# power_section.net
KiCad netlist of a schematic drawn in Altium Designer
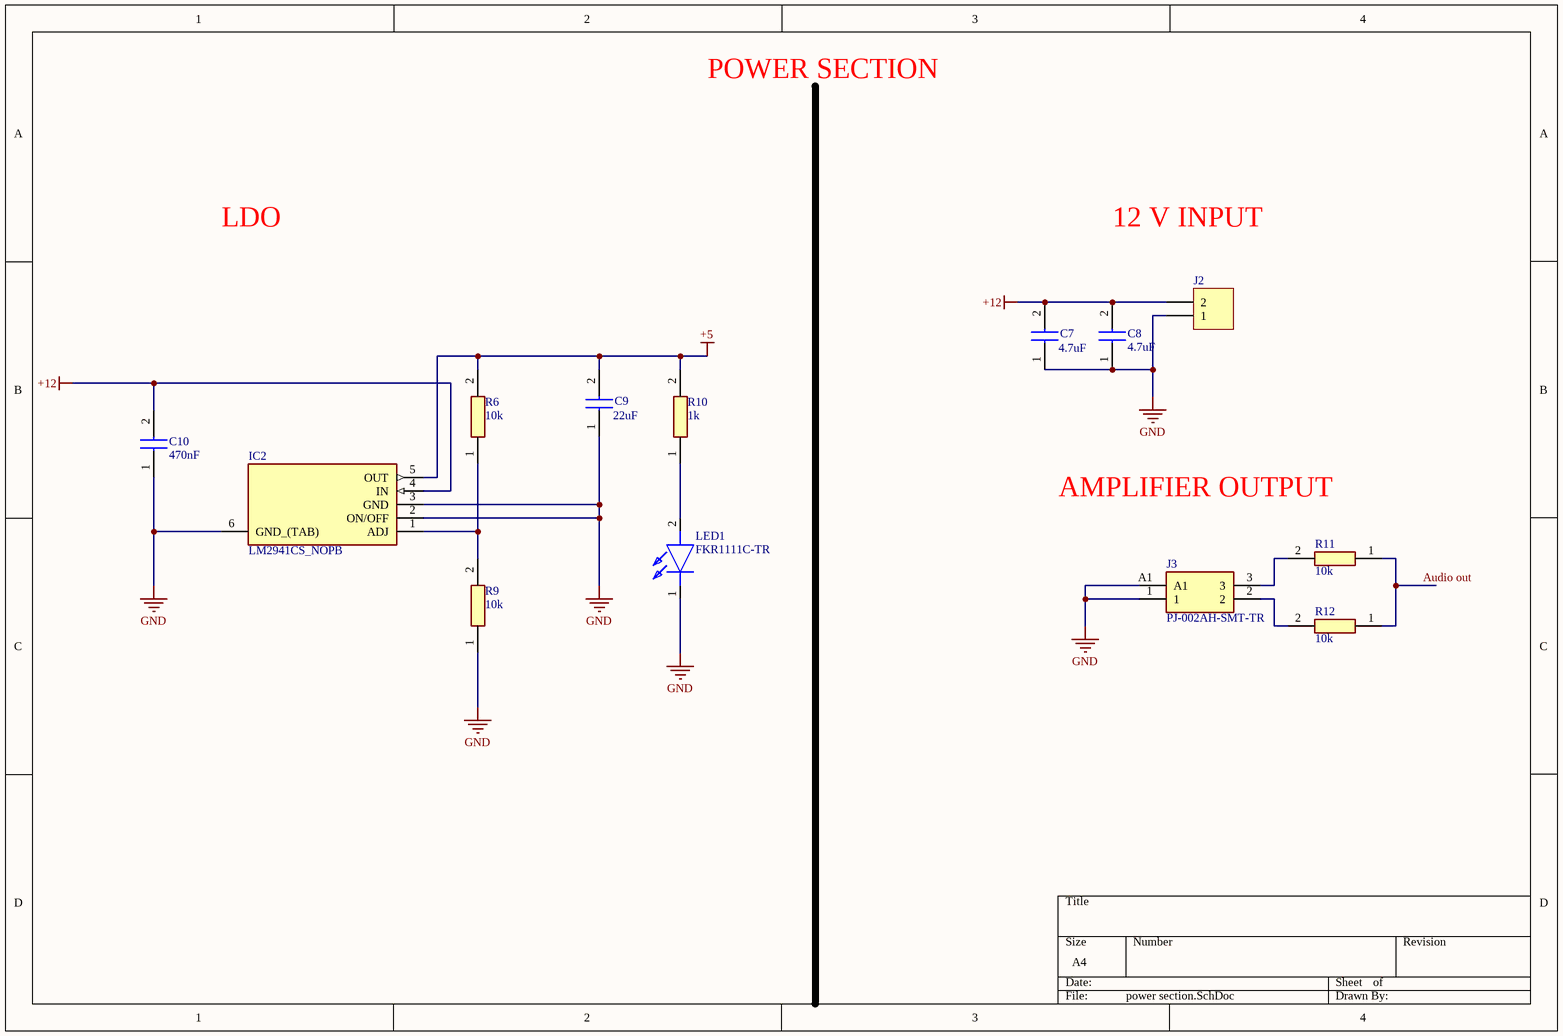
[diagram p0: power section.SchDoc]

(export (version "E")
  (design (tool "Eeschema 10.0.6"))
  (components
    (comp (ref "C7")
      (value "4.7uF")
      (footprint "SamacSys:CAPC1608X90N")
      (description "Capacitor")
      (fields
        (field (name "MANUFACTURER_PART_NUMBER") "GRM188R71C104MA01D")
        (field (name "MOUSER PART NUMBER") "81-GRM18R71C104MA01D")
      )
      (libsource (lib "SamacSys") (part "GRM188R71C104MA01D"))
    )
    (comp (ref "C8")
      (value "4.7uF")
      (footprint "SamacSys:CAPC1608X90N")
      (description "Capacitor")
      (fields
        (field (name "MANUFACTURER_PART_NUMBER") "GRM188R71C104MA01D")
        (field (name "MOUSER PART NUMBER") "81-GRM18R71C104MA01D")
      )
      (libsource (lib "SamacSys") (part "GRM188R71C104MA01D"))
    )
    (comp (ref "C9")
      (value "22uF")
      (footprint "SamacSys:CAPC1608X90N")
      (description "Capacitor")
      (fields
        (field (name "MANUFACTURER_PART_NUMBER") "GRM188R71C104MA01D")
        (field (name "MOUSER PART NUMBER") "81-GRM18R71C104MA01D")
      )
      (libsource (lib "SamacSys") (part "GRM188R71C104MA01D"))
    )
    (comp (ref "C10")
      (value "470nF")
      (footprint "SamacSys:CAPC1608X90N")
      (description "Capacitor")
      (fields
        (field (name "MANUFACTURER_PART_NUMBER") "GRM188R71C104MA01D")
        (field (name "MOUSER PART NUMBER") "81-GRM18R71C104MA01D")
      )
      (libsource (lib "SamacSys") (part "GRM188R71C104MA01D"))
    )
    (comp (ref "IC2")
      (value "LM2941CS_NOPB")
      (footprint "SamacSys:TO170P1435X465-6N")
      (description "Integrated Circuit")
      (fields
        (field (name "MANUFACTURER_PART_NUMBER") "LM2941CS/NOPB")
        (field (name "MOUSER PART NUMBER") "926-LM2941CS/NOPB")
      )
      (libsource (lib "*") (part "LM2941CS_NOPB"))
    )
    (comp (ref "J2")
      (value "~")
      (footprint "CON2_P196_1729128_TH_ST")
      (description "2 Pins, 1 Row 5mm Pitch, straight Connector, male")
      (fields
        (field (name "MANUFACTURER") "Phoenix Contact")
        (field (name "MANUFACTURER PART NUMBER") "MKDSN1,5/2")
      )
      (libsource (lib "CONTROLYTICS") (part "CON-TB_2X1-196-ST-TH"))
    )
    (comp (ref "J3")
      (value "PJ-002AH-SMT-TR")
      (footprint "SamacSys:PJ002AHSMTTR")
      (description "Connector")
      (fields (field (name "MOUSER PART NUMBER") "490-PJ-002AH-SMT-TR"))
      (libsource (lib "SamacSys") (part "PJ-002AH-SMT-TR"))
    )
    (comp (ref "LED1")
      (value "FKR1111C-TR")
      (footprint "SamacSys:LEDC1608X80N")
      (description "LED")
      (fields (field (name "MOUSER PART NUMBER") "327-FKR1111CTR"))
      (libsource (lib "SamacSys") (part "FKR1111C-TR"))
    )
    (comp (ref "R6")
      (value "10k")
      (footprint "SamacSys:ERA3AEB101V")
      (description "Resistor")
      (fields
        (field (name "MANUFACTURER_PART_NUMBER") "ERA-3AED102V")
        (field (name "MOUSER PART NUMBER") "667-ERA-3AED102V")
      )
      (libsource (lib "SamacSys") (part "ERA-3AED102V"))
    )
    (comp (ref "R9")
      (value "10k")
      (footprint "SamacSys:ERA3AEB101V")
      (description "Resistor")
      (fields
        (field (name "MANUFACTURER_PART_NUMBER") "ERA-3AED102V")
        (field (name "MOUSER PART NUMBER") "667-ERA-3AED102V")
      )
      (libsource (lib "SamacSys") (part "ERA-3AED102V"))
    )
    (comp (ref "R10")
      (value "1k")
      (footprint "SamacSys:ERA3AEB101V")
      (description "Resistor")
      (fields
        (field (name "MANUFACTURER_PART_NUMBER") "ERA-3AED102V")
        (field (name "MOUSER PART NUMBER") "667-ERA-3AED102V")
      )
      (libsource (lib "SamacSys") (part "ERA-3AED102V"))
    )
    (comp (ref "R11")
      (value "10k")
      (footprint "SamacSys:ERA3AEB101V")
      (description "Resistor")
      (fields
        (field (name "MANUFACTURER_PART_NUMBER") "ERA-3AED102V")
        (field (name "MOUSER PART NUMBER") "667-ERA-3AED102V")
      )
      (libsource (lib "") (part "ERA-3AED102V_1"))
    )
    (comp (ref "R12")
      (value "10k")
      (footprint "SamacSys:ERA3AEB101V")
      (description "Resistor")
      (fields
        (field (name "MANUFACTURER_PART_NUMBER") "ERA-3AED102V")
        (field (name "MOUSER PART NUMBER") "667-ERA-3AED102V")
      )
      (libsource (lib "") (part "ERA-3AED102V_1"))
    )
  )
  (nets
    (net (code "1") (name "+5") (class "Default")
      (node (ref "C9") (pin "2") (pinfunction "2_2") (pintype "passive"))
      (node (ref "IC2") (pin "5") (pinfunction "OUT_5") (pintype "output"))
      (node (ref "R10") (pin "2") (pinfunction "2_2") (pintype "passive"))
      (node (ref "R6") (pin "2") (pinfunction "2_2") (pintype "passive"))
    )
    (net (code "2") (name "+12") (class "Default")
      (node (ref "C10") (pin "2") (pinfunction "2_2") (pintype "passive"))
      (node (ref "C7") (pin "2") (pinfunction "2_2") (pintype "passive"))
      (node (ref "C8") (pin "2") (pinfunction "2_2") (pintype "passive"))
      (node (ref "IC2") (pin "4") (pinfunction "IN_4") (pintype "input"))
      (node (ref "J2") (pin "2") (pinfunction "2_2") (pintype "passive"))
    )
    (net (code "3") (name "/Audio out") (class "Default")
      (node (ref "R11") (pin "1") (pinfunction "1_1") (pintype "passive"))
      (node (ref "R12") (pin "1") (pinfunction "1_1") (pintype "passive"))
    )
    (net (code "4") (name "GND") (class "Default")
      (node (ref "C10") (pin "1") (pinfunction "1_1") (pintype "passive"))
      (node (ref "C7") (pin "1") (pinfunction "1_1") (pintype "passive"))
      (node (ref "C8") (pin "1") (pinfunction "1_1") (pintype "passive"))
      (node (ref "C9") (pin "1") (pinfunction "1_1") (pintype "passive"))
      (node (ref "IC2") (pin "2") (pinfunction "ON/OFF_2") (pintype "passive"))
      (node (ref "IC2") (pin "3") (pinfunction "GND_3") (pintype "power_in"))
      (node (ref "IC2") (pin "6") (pinfunction "GND_(TAB)_6") (pintype "power_in"))
      (node (ref "J2") (pin "1") (pinfunction "1_1") (pintype "passive"))
      (node (ref "J3") (pin "1") (pinfunction "1_1") (pintype "passive"))
      (node (ref "J3") (pin "A1") (pinfunction "A1_A1") (pintype "passive"))
      (node (ref "LED1") (pin "1") (pinfunction "K_1") (pintype "passive"))
      (node (ref "R9") (pin "1") (pinfunction "1_1") (pintype "passive"))
    )
    (net (code "5") (name "Net-(IC2-ADJ)") (class "Default")
      (node (ref "IC2") (pin "1") (pinfunction "ADJ_1") (pintype "passive"))
      (node (ref "R6") (pin "1") (pinfunction "1_1") (pintype "passive"))
      (node (ref "R9") (pin "2") (pinfunction "2_2") (pintype "passive"))
    )
    (net (code "6") (name "Net-(J3-Pad2)") (class "Default")
      (node (ref "J3") (pin "2") (pinfunction "2_2") (pintype "passive"))
      (node (ref "R12") (pin "2") (pinfunction "2_2") (pintype "passive"))
    )
    (net (code "7") (name "Net-(J3-Pad3)") (class "Default")
      (node (ref "J3") (pin "3") (pinfunction "3_3") (pintype "passive"))
      (node (ref "R11") (pin "2") (pinfunction "2_2") (pintype "passive"))
    )
    (net (code "8") (name "Net-(LED1-A)") (class "Default")
      (node (ref "LED1") (pin "2") (pinfunction "A_2") (pintype "passive"))
      (node (ref "R10") (pin "1") (pinfunction "1_1") (pintype "passive"))
    )
  )
)
